# Sense_3_Signal_Isolation.net
KiCad netlist of a schematic drawn in Altium Designer
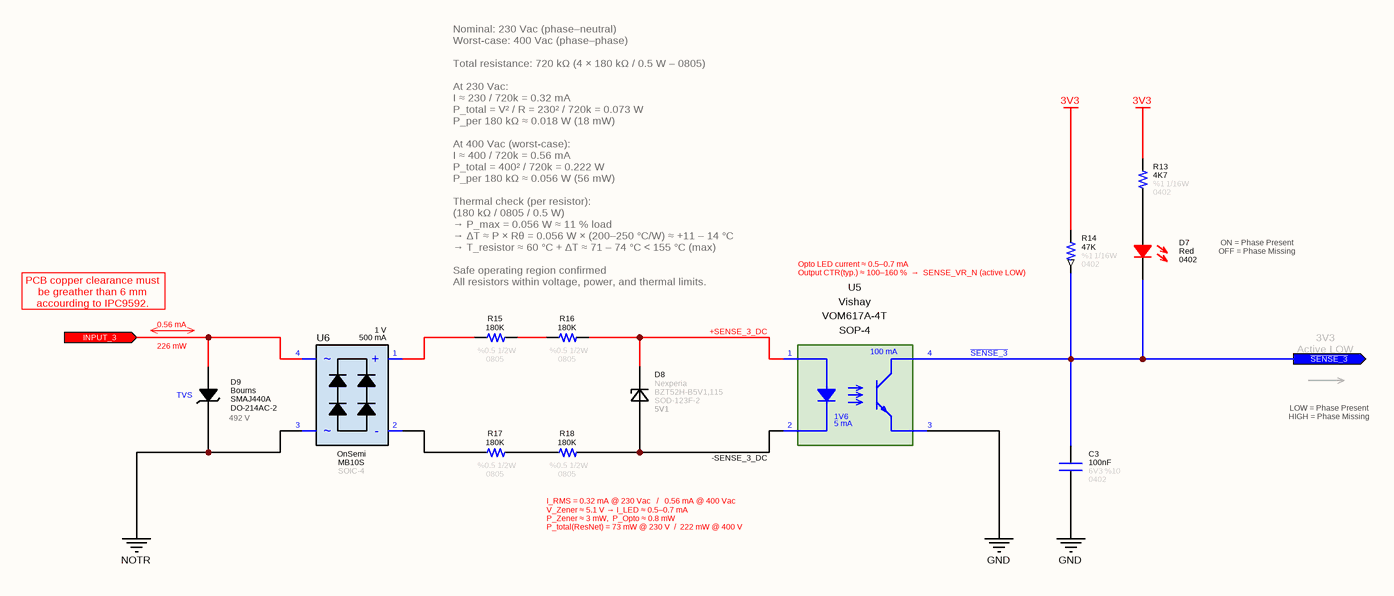
[diagram p0: Sense 3 Signal Isolation.SchDoc]

(export (version "E")
  (design (tool "Eeschema 10.0.6"))
  (components
    (comp (ref "C3")
      (value "100nF")
      (footprint "CAPACITOR_0402")
      (description "Capacitor (MLCC) - 100nF / 6V3 / 0402")
      (fields
        (field (name "MANUFACTURER PART NUMBER") "04026D104KAT4A")
        (field (name "TOLERANCE") "%10")
        (field (name "VOLTAGE") "6V3")
        (field (name "CASE") "0402")
        (field (name "Comment") "Capacitor - 100nF [0402] (MLCC)")
      )
      (libsource (lib "Akkoyun") (part "Capacitor - 100nF [0402-6V3]"))
    )
    (comp (ref "D7")
      (value "SMD LED (Red)")
      (footprint "LED_0402")
      (description "Standard LEDs - SMD MINI-MOLD ULTRA COMPACT RED")
      (fields
        (field (name "MANUFACTURER PART NUMBER") "SML-P12VTT86R")
        (field (name "CASE") "0402")
        (field (name "COLOR") "Red")
      )
      (libsource (lib "Akkoyun") (part "Diode - LED (0402-Red)"))
    )
    (comp (ref "D8")
      (value "BZT52H-B5V1,115")
      (footprint "SOD-123F-2")
      (description "Zener Diodes BZT52H-B5V1/SOD123F/SOD2")
      (fields
        (field (name "ZENER VOLTAGE") "5V1")
        (field (name "MANUFACTURER NAME") "Nexperia")
        (field (name "MANUFACTURER PART NUMBER") "BZT52H-B5V1,115")
        (field (name "CASE") "SOD-123F-2")
      )
      (libsource (lib "Akkoyun") (part "Diode - BZT52H-B5V1,115"))
    )
    (comp (ref "D9")
      (value "SMAJ440A")
      (footprint "DO-220AA-2")
      (description "ESD Protection Diodes / TVS Diodes 440volts 1uA .6 Amps Uni-Dir")
      (fields
        (field (name "BREAKDOWN VOLTAGE") "492 V")
        (field (name "MANUFACTURER NAME") "Bourns")
        (field (name "MANUFACTURER PART NUMBER") "SMAJ440A")
        (field (name "CASE") "DO-214AC-2")
      )
      (libsource (lib "Akkoyun") (part "Diode - SMAJ440A (TVS)"))
    )
    (comp (ref "R13")
      (value "4K7")
      (footprint "RESISTOR_0402")
      (description "Thick Film Resistors - SMD 1/16 W 4.7 KOhm 1%")
      (fields
        (field (name "MANUFACTURER PART NUMBER") "CRCW04024K70FKED")
        (field (name "TOLERANCE") "%1")
        (field (name "CASE") "0402")
        (field (name "POWER") "1/16W")
        (field (name "Comment") "4K7 - 0402 - %1 - 1/16W")
      )
      (libsource (lib "Akkoyun") (part "Resistor - 4K7 [0402]"))
    )
    (comp (ref "R14")
      (value "47K")
      (footprint "RESISTOR_0402")
      (description "Thick Film Resistors - SMD 1/16 W 47 KOhm 1%")
      (fields
        (field (name "MANUFACTURER PART NUMBER") "CRCW040247K0FKED")
        (field (name "TOLERANCE") "%1")
        (field (name "CASE") "0402")
        (field (name "POWER") "1/16W")
        (field (name "Comment") "47K - 0402 - %1 - 1/16W")
      )
      (libsource (lib "Akkoyun") (part "Resistor - 47K [0402]"))
    )
    (comp (ref "R15")
      (value "180K")
      (footprint "RESISTOR_0805")
      (description "Thick Film Resistors - SMD 0805 180Kohms 0.5W 0.5% AEC-Q200")
      (fields
        (field (name "MANUFACTURER PART NUMBER") "ERJ-P06D1803V")
        (field (name "TOLERANCE") "%0.5")
        (field (name "CASE") "0805")
        (field (name "POWER") "1/2W")
        (field (name "Comment") "180K - 0805 - %0.5 - 1/2W")
      )
      (libsource (lib "Akkoyun") (part "Resistor - 180K [0805]"))
    )
    (comp (ref "R16")
      (value "180K")
      (footprint "RESISTOR_0805")
      (description "Thick Film Resistors - SMD 0805 180Kohms 0.5W 0.5% AEC-Q200")
      (fields
        (field (name "MANUFACTURER PART NUMBER") "ERJ-P06D1803V")
        (field (name "TOLERANCE") "%0.5")
        (field (name "CASE") "0805")
        (field (name "POWER") "1/2W")
        (field (name "Comment") "180K - 0805 - %0.5 - 1/2W")
      )
      (libsource (lib "Akkoyun") (part "Resistor - 180K [0805]"))
    )
    (comp (ref "R17")
      (value "180K")
      (footprint "RESISTOR_0805")
      (description "Thick Film Resistors - SMD 0805 180Kohms 0.5W 0.5% AEC-Q200")
      (fields
        (field (name "MANUFACTURER PART NUMBER") "ERJ-P06D1803V")
        (field (name "TOLERANCE") "%0.5")
        (field (name "CASE") "0805")
        (field (name "POWER") "1/2W")
        (field (name "Comment") "180K - 0805 - %0.5 - 1/2W")
      )
      (libsource (lib "Akkoyun") (part "Resistor - 180K [0805]"))
    )
    (comp (ref "R18")
      (value "180K")
      (footprint "RESISTOR_0805")
      (description "Thick Film Resistors - SMD 0805 180Kohms 0.5W 0.5% AEC-Q200")
      (fields
        (field (name "MANUFACTURER PART NUMBER") "ERJ-P06D1803V")
        (field (name "TOLERANCE") "%0.5")
        (field (name "CASE") "0805")
        (field (name "POWER") "1/2W")
        (field (name "Comment") "180K - 0805 - %0.5 - 1/2W")
      )
      (libsource (lib "Akkoyun") (part "Resistor - 180K [0805]"))
    )
    (comp (ref "U5")
      (value "VOM617A-4T")
      (footprint "SOP-4V2")
      (description "Transistor Output Optocouplers Phototransistor Out CTR 160-320% 5mA")
      (fields
        (field (name "MANUFACTURER PART NUMBER") "VOM617A-4T")
        (field (name "MANUFACTURER NAME") "Vishay")
        (field (name "CASE") "SOP-4")
        (field (name "IF - FORWARD CURRENT") "5 mA")
        (field (name "VF - FORWARD VOLTAGE") "1V6")
        (field (name "MAXIMUM COLLECTOR CURRENT") "100 mA")
      )
      (libsource (lib "Akkoyun") (part "IC - VOM617A"))
    )
    (comp (ref "U6")
      (value "LTV-846S")
      (footprint "SOIC-4")
      (description "Transistor Output Optocouplers Optocplr Phototrans 4-Channel")
      (fields
        (field (name "IF - FORWARD CURRENT") "500 mA")
        (field (name "VF - FORWARD VOLTAGE") "1 V")
        (field (name "MANUFACTURER NAME") "OnSemi")
        (field (name "MANUFACTURER PART NUMBER") "MB10S")
        (field (name "CASE") "SOIC-4")
      )
      (libsource (lib "Akkoyun") (part "IC - MB10S"))
    )
  )
  (nets
    (net (code "1") (name "/+SENSE_3_DC") (class "Default")
      (node (ref "D8") (pin "1") (pinfunction "Cathode_1") (pintype "passive"))
      (node (ref "R16") (pin "1") (pinfunction "1_1") (pintype "passive"))
      (node (ref "U5") (pin "1") (pinfunction "LED_Anode_1") (pintype "passive"))
    )
    (net (code "2") (name "/-SENSE_3_DC") (class "Default")
      (node (ref "D8") (pin "2") (pinfunction "Anode_2") (pintype "passive"))
      (node (ref "R18") (pin "1") (pinfunction "1_1") (pintype "passive"))
      (node (ref "U5") (pin "2") (pinfunction "LED_Cathode_2") (pintype "passive"))
    )
    (net (code "3") (name "/INPUT_3") (class "Default")
      (node (ref "D9") (pin "1") (pinfunction "Anode_1") (pintype "passive"))
      (node (ref "U6") (pin "4") (pinfunction "~_4") (pintype "passive"))
    )
    (net (code "4") (name "/~{SENSE_3}") (class "Default")
      (node (ref "C3") (pin "2") (pinfunction "2_2") (pintype "passive"))
      (node (ref "D7") (pin "1") (pinfunction "1_1") (pintype "passive"))
      (node (ref "R14") (pin "1") (pinfunction "1_1") (pintype "output"))
      (node (ref "U5") (pin "4") (pinfunction "Collector_4") (pintype "passive"))
    )
    (net (code "5") (name "3V3") (class "Default")
      (node (ref "R13") (pin "2") (pinfunction "2_2") (pintype "passive"))
      (node (ref "R14") (pin "2") (pinfunction "2_2") (pintype "passive"))
    )
    (net (code "6") (name "GND") (class "Default")
      (node (ref "C3") (pin "1") (pinfunction "1_1") (pintype "passive"))
      (node (ref "U5") (pin "3") (pinfunction "Emiter_3") (pintype "passive"))
    )
    (net (code "7") (name "NOTR") (class "Default")
      (node (ref "D9") (pin "2") (pinfunction "Cathode_2") (pintype "passive"))
      (node (ref "U6") (pin "3") (pinfunction "~_3") (pintype "passive"))
    )
    (net (code "8") (name "Net-(D7-Pad2)") (class "Default")
      (node (ref "D7") (pin "2") (pinfunction "2_2") (pintype "passive"))
      (node (ref "R13") (pin "1") (pinfunction "1_1") (pintype "passive"))
    )
    (net (code "9") (name "Net-(R15-Pad1)") (class "Default")
      (node (ref "R15") (pin "1") (pinfunction "1_1") (pintype "passive"))
      (node (ref "R16") (pin "2") (pinfunction "2_2") (pintype "passive"))
    )
    (net (code "10") (name "Net-(R17-Pad1)") (class "Default")
      (node (ref "R17") (pin "1") (pinfunction "1_1") (pintype "passive"))
      (node (ref "R18") (pin "2") (pinfunction "2_2") (pintype "passive"))
    )
    (net (code "11") (name "Net-(U6-+)") (class "Default")
      (node (ref "R15") (pin "2") (pinfunction "2_2") (pintype "passive"))
      (node (ref "U6") (pin "1") (pinfunction "+_1") (pintype "passive"))
    )
    (net (code "12") (name "Net-(U6--)") (class "Default")
      (node (ref "R17") (pin "2") (pinfunction "2_2") (pintype "passive"))
      (node (ref "U6") (pin "2") (pinfunction "-_2") (pintype "passive"))
    )
  )
)
